# RA08T.net
KiCad netlist of a schematic drawn in Altium Designer
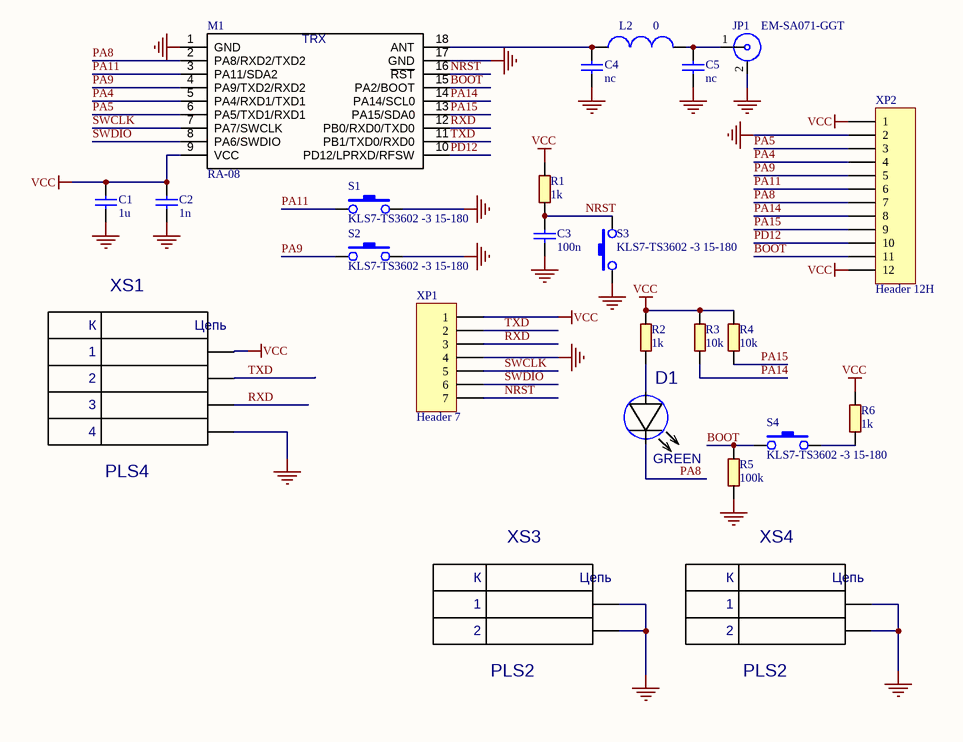
[diagram p0: RA08T.SchDoc]

(export (version "E")
  (design (tool "Eeschema 10.0.6"))
  (components
    (comp (ref "C1")
      (value "1u")
      (footprint "C-0603")
      (fields (field (name "VOLTAGE") "50V"))
      (libsource (lib "Passive") (part "CAPN"))
    )
    (comp (ref "C2")
      (value "1n")
      (footprint "C-0603")
      (fields (field (name "VOLTAGE") "50V"))
      (libsource (lib "Passive") (part "CAPN"))
    )
    (comp (ref "C3")
      (value "100n")
      (footprint "C-0603")
      (fields (field (name "VOLTAGE") "50V"))
      (libsource (lib "Passive") (part "CAPN"))
    )
    (comp (ref "C4")
      (value "nc")
      (footprint "C-0603")
      (fields (field (name "VOLTAGE") "50V"))
      (libsource (lib "Passive") (part "CAPN"))
    )
    (comp (ref "C5")
      (value "nc")
      (footprint "C-0603")
      (fields (field (name "VOLTAGE") "50V"))
      (libsource (lib "Passive") (part "CAPN"))
    )
    (comp (ref "D1")
      (value "GREEN")
      (footprint "LED_3mm_RED")
      (fields (field (name "Comment") "LED3mm"))
      (libsource (lib "E2002") (part "LED3mm"))
    )
    (comp (ref "JP1")
      (value "EM-SA071-GGT")
      (footprint "AMPHENOL_132357-11")
      (description "SMA Female R/A PCB Mount")
      (libsource (lib "Connectors") (part "SMA"))
    )
    (comp (ref "L2") (value "0") (footprint "L-0603") (libsource (lib "Passive") (part "L")))
    (comp (ref "M1") (value "RA-08") (footprint "LGA18_RA08") (libsource (lib "RA08T") (part "RA-08")))
    (comp (ref "R1") (value "1k") (footprint "R-0603") (libsource (lib "Passive") (part "RES")))
    (comp (ref "R2") (value "1k") (footprint "R-0603") (libsource (lib "Passive") (part "RES")))
    (comp (ref "R3") (value "10k") (footprint "R-0603") (libsource (lib "Passive") (part "RES")))
    (comp (ref "R4") (value "10k") (footprint "R-0603") (libsource (lib "Passive") (part "RES")))
    (comp (ref "R5") (value "100k") (footprint "R-0603") (libsource (lib "") (part "RES_1")))
    (comp (ref "R6") (value "1k") (footprint "R-0603") (libsource (lib "") (part "RES_1")))
    (comp (ref "S1")
      (value "KLS7-TS3602 -3 15-180")
      (footprint "BUTT_MIN")
      (libsource (lib "Switches") (part "SW-1"))
    )
    (comp (ref "S2")
      (value "KLS7-TS3602 -3 15-180")
      (footprint "BUTT_MIN")
      (libsource (lib "Switches") (part "SW-1"))
    )
    (comp (ref "S3")
      (value "KLS7-TS3602 -3 15-180")
      (footprint "BUTT_MIN")
      (libsource (lib "Switches") (part "SW-1"))
    )
    (comp (ref "S4")
      (value "KLS7-TS3602 -3 15-180")
      (footprint "BUTT_MIN")
      (libsource (lib "Switches") (part "SW-1"))
    )
    (comp (ref "XP1")
      (value "Header 7")
      (footprint "PLS1-7R")
      (description "Header, 7-Pin")
      (fields (field (name "PUBLISHER") "Altium Limited"))
      (libsource (lib "Miscellaneous Connectors") (part "Header 7"))
    )
    (comp (ref "XP2")
      (value "Header 12H")
      (footprint "HDR1X12H_1")
      (description "Header, 12-Pin, Right Angle")
      (fields (field (name "PUBLISHER") "Altium Limited"))
      (libsource (lib "Miscellaneous Connectors") (part "Header 12H"))
    )
    (comp (ref "XS1") (value "PLS4") (footprint "PLS4 - 3D") (libsource (lib "E2002") (part "PLS4")))
    (comp (ref "XS3") (value "PLS2") (footprint "PLS2 - 3D") (libsource (lib "E2002") (part "PLS2")))
    (comp (ref "XS4") (value "PLS2") (footprint "PLS2 - 3D") (libsource (lib "E2002") (part "PLS2")))
  )
  (nets
    (net (code "1") (name "/BOOT") (class "Default")
      (node (ref "M1") (pin "15") (pinfunction "PA2/BOOT_15") (pintype "passive"))
      (node (ref "R5") (pin "1") (pinfunction "1_1") (pintype "passive"))
      (node (ref "S4") (pin "1") (pinfunction "1_1") (pintype "passive"))
      (node (ref "XP2") (pin "11") (pinfunction "11_11") (pintype "passive"))
    )
    (net (code "2") (name "/NRST") (class "Default")
      (node (ref "C3") (pin "1") (pinfunction "1_1") (pintype "passive"))
      (node (ref "M1") (pin "16") (pinfunction "~{RST}_16") (pintype "passive"))
      (node (ref "R1") (pin "1") (pinfunction "1_1") (pintype "passive"))
      (node (ref "S3") (pin "2") (pinfunction "2_2") (pintype "passive"))
      (node (ref "XP1") (pin "7") (pinfunction "7_7") (pintype "passive"))
    )
    (net (code "3") (name "/PA4") (class "Default")
      (node (ref "M1") (pin "5") (pinfunction "PA4/RXD1/TXD1_5") (pintype "passive"))
      (node (ref "XP2") (pin "4") (pinfunction "4_4") (pintype "passive"))
    )
    (net (code "4") (name "/PA5") (class "Default")
      (node (ref "M1") (pin "6") (pinfunction "PA5/TXD1/RXD1_6") (pintype "passive"))
      (node (ref "XP2") (pin "3") (pinfunction "3_3") (pintype "passive"))
    )
    (net (code "5") (name "/PA8") (class "Default")
      (node (ref "D1") (pin "2") (pinfunction "2_2") (pintype "passive"))
      (node (ref "M1") (pin "2") (pinfunction "PA8/RXD2/TXD2_2") (pintype "passive"))
      (node (ref "XP2") (pin "7") (pinfunction "7_7") (pintype "passive"))
    )
    (net (code "6") (name "/PA9") (class "Default")
      (node (ref "M1") (pin "4") (pinfunction "PA9/TXD2/RXD2_4") (pintype "passive"))
      (node (ref "S2") (pin "1") (pinfunction "1_1") (pintype "passive"))
      (node (ref "XP2") (pin "5") (pinfunction "5_5") (pintype "passive"))
    )
    (net (code "7") (name "/PA11") (class "Default")
      (node (ref "M1") (pin "3") (pinfunction "PA11/SDA2_3") (pintype "passive"))
      (node (ref "S1") (pin "1") (pinfunction "1_1") (pintype "passive"))
      (node (ref "XP2") (pin "6") (pinfunction "6_6") (pintype "passive"))
    )
    (net (code "8") (name "/PA14") (class "Default")
      (node (ref "M1") (pin "14") (pinfunction "PA14/SCL0_14") (pintype "passive"))
      (node (ref "R3") (pin "1") (pinfunction "1_1") (pintype "passive"))
      (node (ref "XP2") (pin "8") (pinfunction "8_8") (pintype "passive"))
    )
    (net (code "9") (name "/PA15") (class "Default")
      (node (ref "M1") (pin "13") (pinfunction "PA15/SDA0_13") (pintype "passive"))
      (node (ref "R4") (pin "1") (pinfunction "1_1") (pintype "passive"))
      (node (ref "XP2") (pin "9") (pinfunction "9_9") (pintype "passive"))
    )
    (net (code "10") (name "/PD12") (class "Default")
      (node (ref "M1") (pin "10") (pinfunction "PD12/LPRXD/RFSW_10") (pintype "passive"))
      (node (ref "XP2") (pin "10") (pinfunction "10_10") (pintype "passive"))
    )
    (net (code "11") (name "/RXD") (class "Default")
      (node (ref "M1") (pin "12") (pinfunction "PB0/RXD0/TXD0_12") (pintype "passive"))
      (node (ref "XP1") (pin "3") (pinfunction "3_3") (pintype "passive"))
      (node (ref "XS1") (pin "3") (pinfunction "3_3") (pintype "passive"))
    )
    (net (code "12") (name "/SWCLK") (class "Default")
      (node (ref "M1") (pin "7") (pinfunction "PA7/SWCLK_7") (pintype "passive"))
      (node (ref "XP1") (pin "5") (pinfunction "5_5") (pintype "passive"))
    )
    (net (code "13") (name "/SWDIO") (class "Default")
      (node (ref "M1") (pin "8") (pinfunction "PA6/SWDIO_8") (pintype "passive"))
      (node (ref "XP1") (pin "6") (pinfunction "6_6") (pintype "passive"))
    )
    (net (code "14") (name "/TXD") (class "Default")
      (node (ref "M1") (pin "11") (pinfunction "PB1/TXD0/RXD0_11") (pintype "passive"))
      (node (ref "XP1") (pin "2") (pinfunction "2_2") (pintype "passive"))
      (node (ref "XS1") (pin "2") (pinfunction "2_2") (pintype "passive"))
    )
    (net (code "15") (name "GND") (class "Default")
      (node (ref "C1") (pin "2") (pinfunction "2_2") (pintype "passive"))
      (node (ref "C2") (pin "2") (pinfunction "2_2") (pintype "passive"))
      (node (ref "C3") (pin "2") (pinfunction "2_2") (pintype "passive"))
      (node (ref "C4") (pin "2") (pinfunction "2_2") (pintype "passive"))
      (node (ref "C5") (pin "2") (pinfunction "2_2") (pintype "passive"))
      (node (ref "JP1") (pin "2") (pinfunction "2_2") (pintype "passive"))
      (node (ref "M1") (pin "1") (pinfunction "GND_1") (pintype "passive"))
      (node (ref "M1") (pin "17") (pinfunction "GND_17") (pintype "passive"))
      (node (ref "R5") (pin "2") (pinfunction "2_2") (pintype "passive"))
      (node (ref "S1") (pin "2") (pinfunction "2_2") (pintype "passive"))
      (node (ref "S2") (pin "2") (pinfunction "2_2") (pintype "passive"))
      (node (ref "S3") (pin "1") (pinfunction "1_1") (pintype "passive"))
      (node (ref "XP1") (pin "4") (pinfunction "4_4") (pintype "passive"))
      (node (ref "XP2") (pin "2") (pinfunction "2_2") (pintype "passive"))
      (node (ref "XS1") (pin "4") (pinfunction "4_4") (pintype "passive"))
      (node (ref "XS3") (pin "1") (pinfunction "1_1") (pintype "passive"))
      (node (ref "XS3") (pin "2") (pinfunction "2_2") (pintype "passive"))
      (node (ref "XS4") (pin "1") (pinfunction "1_1") (pintype "passive"))
      (node (ref "XS4") (pin "2") (pinfunction "2_2") (pintype "passive"))
    )
    (net (code "16") (name "Net-(C5-Pad1)") (class "Default")
      (node (ref "C5") (pin "1") (pinfunction "1_1") (pintype "passive"))
      (node (ref "JP1") (pin "1") (pinfunction "1_1") (pintype "passive"))
      (node (ref "L2") (pin "2") (pinfunction "2_2") (pintype "passive"))
    )
    (net (code "17") (name "Net-(D1-Pad1)") (class "Default")
      (node (ref "D1") (pin "1") (pinfunction "1_1") (pintype "passive"))
      (node (ref "R2") (pin "1") (pinfunction "1_1") (pintype "passive"))
    )
    (net (code "18") (name "Net-(M1-ANT)") (class "Default")
      (node (ref "C4") (pin "1") (pinfunction "1_1") (pintype "passive"))
      (node (ref "L2") (pin "1") (pinfunction "1_1") (pintype "passive"))
      (node (ref "M1") (pin "18") (pinfunction "ANT_18") (pintype "passive"))
    )
    (net (code "19") (name "Net-(R6-Pad2)") (class "Default")
      (node (ref "R6") (pin "2") (pinfunction "2_2") (pintype "passive"))
      (node (ref "S4") (pin "2") (pinfunction "2_2") (pintype "passive"))
    )
    (net (code "20") (name "VCC") (class "Default")
      (node (ref "C1") (pin "1") (pinfunction "1_1") (pintype "passive"))
      (node (ref "C2") (pin "1") (pinfunction "1_1") (pintype "passive"))
      (node (ref "M1") (pin "9") (pinfunction "VCC_9") (pintype "passive"))
      (node (ref "R1") (pin "2") (pinfunction "2_2") (pintype "passive"))
      (node (ref "R2") (pin "2") (pinfunction "2_2") (pintype "passive"))
      (node (ref "R3") (pin "2") (pinfunction "2_2") (pintype "passive"))
      (node (ref "R4") (pin "2") (pinfunction "2_2") (pintype "passive"))
      (node (ref "R6") (pin "1") (pinfunction "1_1") (pintype "passive"))
      (node (ref "XP1") (pin "1") (pinfunction "1_1") (pintype "passive"))
      (node (ref "XP2") (pin "1") (pinfunction "1_1") (pintype "passive"))
      (node (ref "XP2") (pin "12") (pinfunction "12_12") (pintype "passive"))
      (node (ref "XS1") (pin "1") (pinfunction "1_1") (pintype "passive"))
    )
  )
)
